# GeneratedSystem-03.net
KiCad netlist of a schematic drawn in Altium Designer
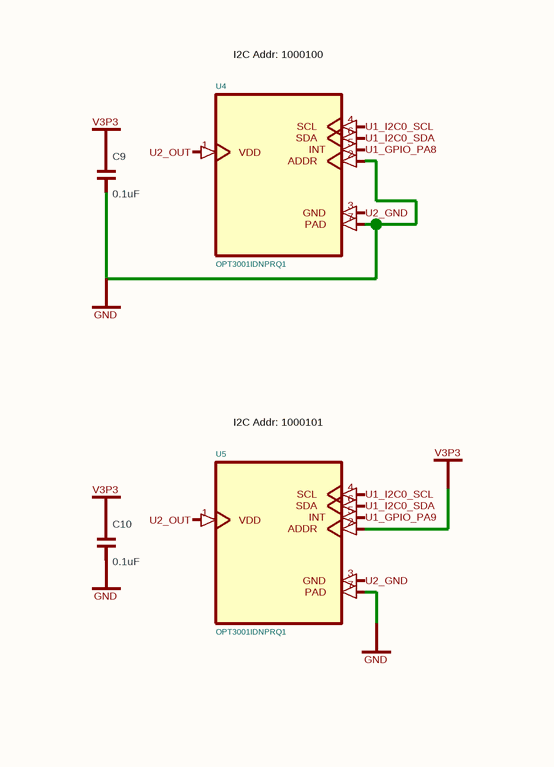
[diagram p0: GeneratedSystem-03.SchDoc]

(export (version "E")
  (design (tool "Eeschema 10.0.6"))
  (components
    (comp (ref "C9") (value "0.1uF") (libsource (lib "altium-import") (part "root_0_capacitor_down_")))
    (comp (ref "C10") (value "0.1uF") (libsource (lib "altium-import") (part "root_0_capacitor_down_")))
    (comp (ref "U4") (value "~") (libsource (lib "altium-import") (part "root_0_U4_")))
    (comp (ref "U5") (value "~") (libsource (lib "altium-import") (part "root_0_U5_")))
  )
  (nets
    (net (code "1") (name "/U1_GPIO_PA8") (class "Default")
      (node (ref "U4") (pin "5") (pinfunction "INT_5") (pintype "input"))
    )
    (net (code "2") (name "/U1_GPIO_PA9") (class "Default")
      (node (ref "U5") (pin "5") (pinfunction "INT_5") (pintype "input"))
    )
    (net (code "3") (name "/U1_I2C0_SCL") (class "Default")
      (node (ref "U4") (pin "4") (pinfunction "SCL_4") (pintype "input"))
      (node (ref "U5") (pin "4") (pinfunction "SCL_4") (pintype "input"))
    )
    (net (code "4") (name "/U1_I2C0_SDA") (class "Default")
      (node (ref "U4") (pin "6") (pinfunction "SDA_6") (pintype "input"))
      (node (ref "U5") (pin "6") (pinfunction "SDA_6") (pintype "input"))
    )
    (net (code "5") (name "/U2_GND") (class "Default")
      (node (ref "U4") (pin "3") (pinfunction "GND_3") (pintype "input"))
      (node (ref "U5") (pin "3") (pinfunction "GND_3") (pintype "input"))
    )
    (net (code "6") (name "/U2_OUT") (class "Default")
      (node (ref "U4") (pin "1") (pinfunction "VDD_1") (pintype "input"))
      (node (ref "U5") (pin "1") (pinfunction "VDD_1") (pintype "input"))
    )
    (net (code "7") (name "GND") (class "Default")
      (node (ref "C10") (pin "2") (pinfunction "cathode_2") (pintype "input"))
      (node (ref "C9") (pin "2") (pinfunction "cathode_2") (pintype "input"))
      (node (ref "U4") (pin "2") (pinfunction "ADDR_2") (pintype "input"))
      (node (ref "U4") (pin "7") (pinfunction "PAD_7") (pintype "input"))
      (node (ref "U5") (pin "7") (pinfunction "PAD_7") (pintype "input"))
    )
    (net (code "8") (name "V3P3") (class "Default")
      (node (ref "C10") (pin "1") (pinfunction "anode_1") (pintype "input"))
      (node (ref "C9") (pin "1") (pinfunction "anode_1") (pintype "input"))
      (node (ref "U5") (pin "2") (pinfunction "ADDR_2") (pintype "input"))
    )
  )
)
